# 2012_BALISE_CARTE_EMETTEUR.net
KiCad netlist of a schematic drawn in Altium Designer
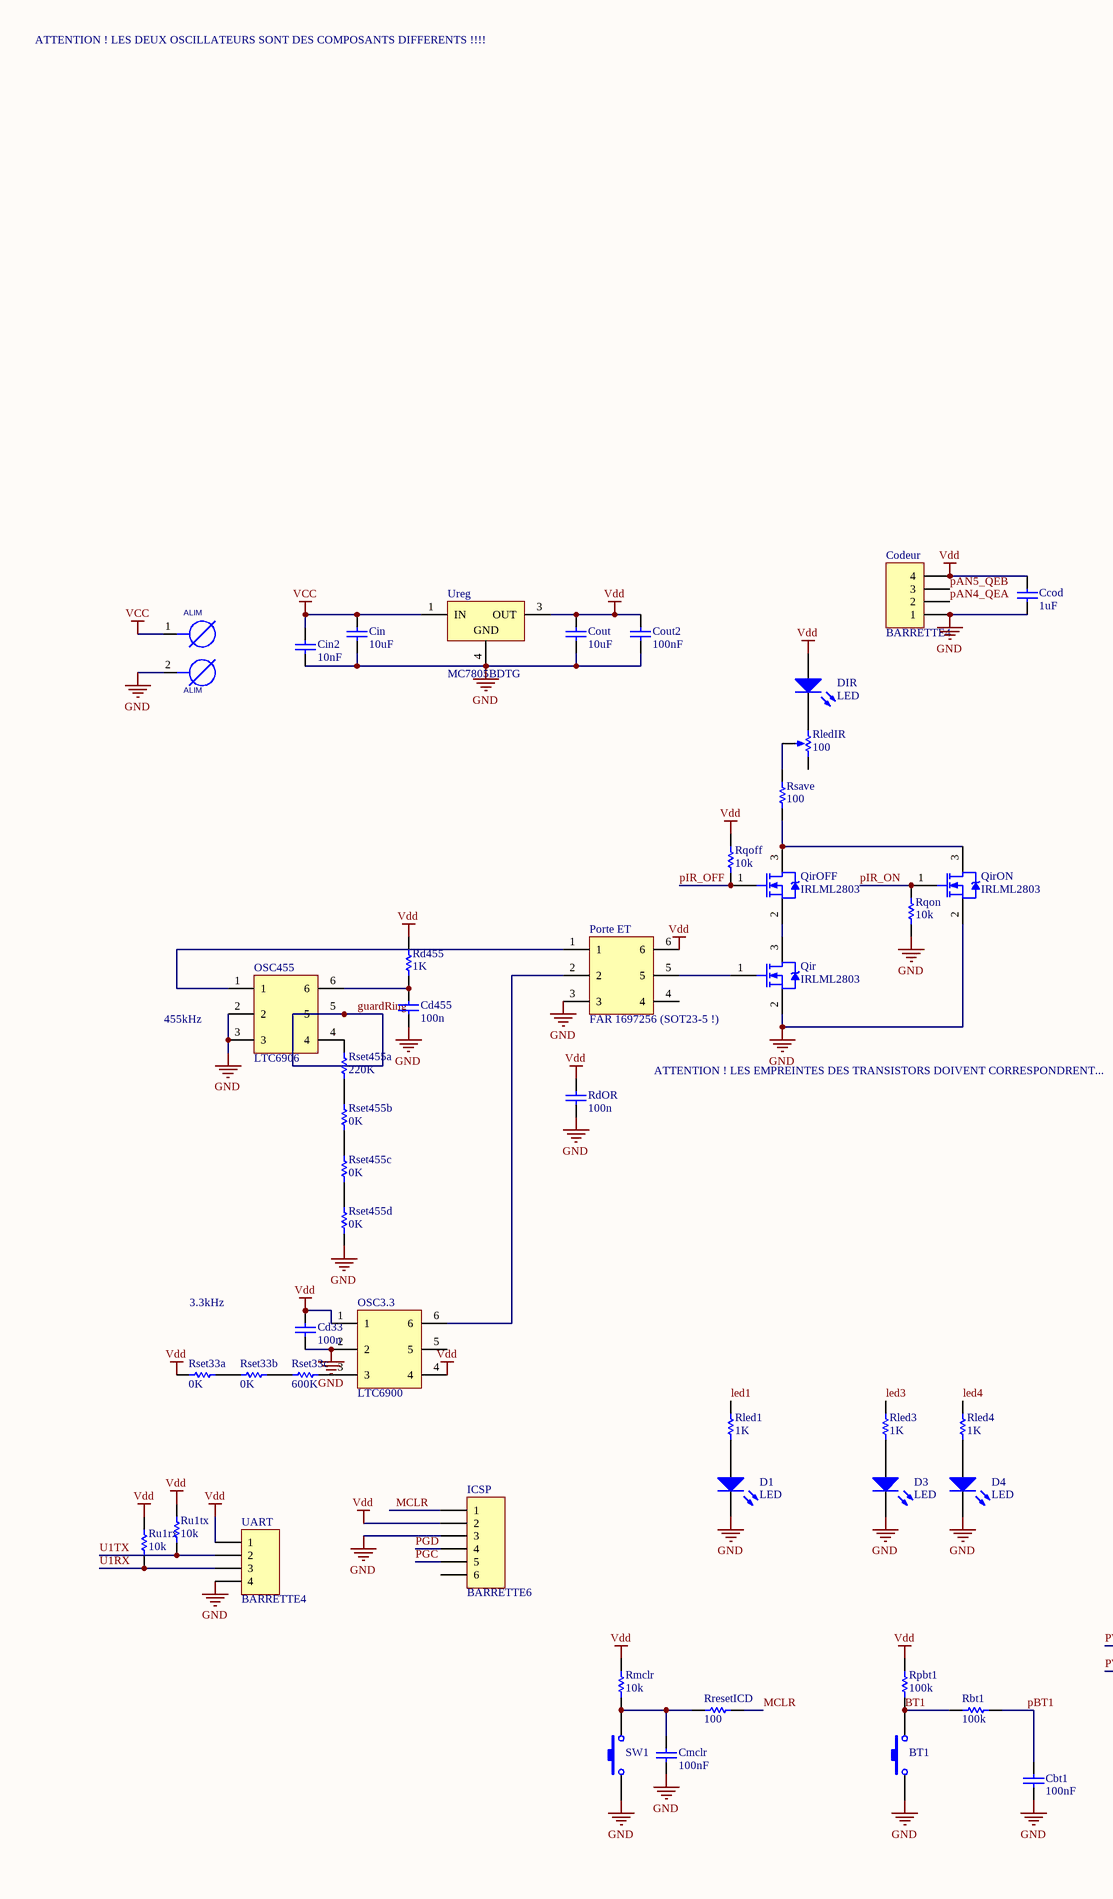
[diagram p0: 2012_BALISE_CARTE_EMETTEUR.SchDoc, left]
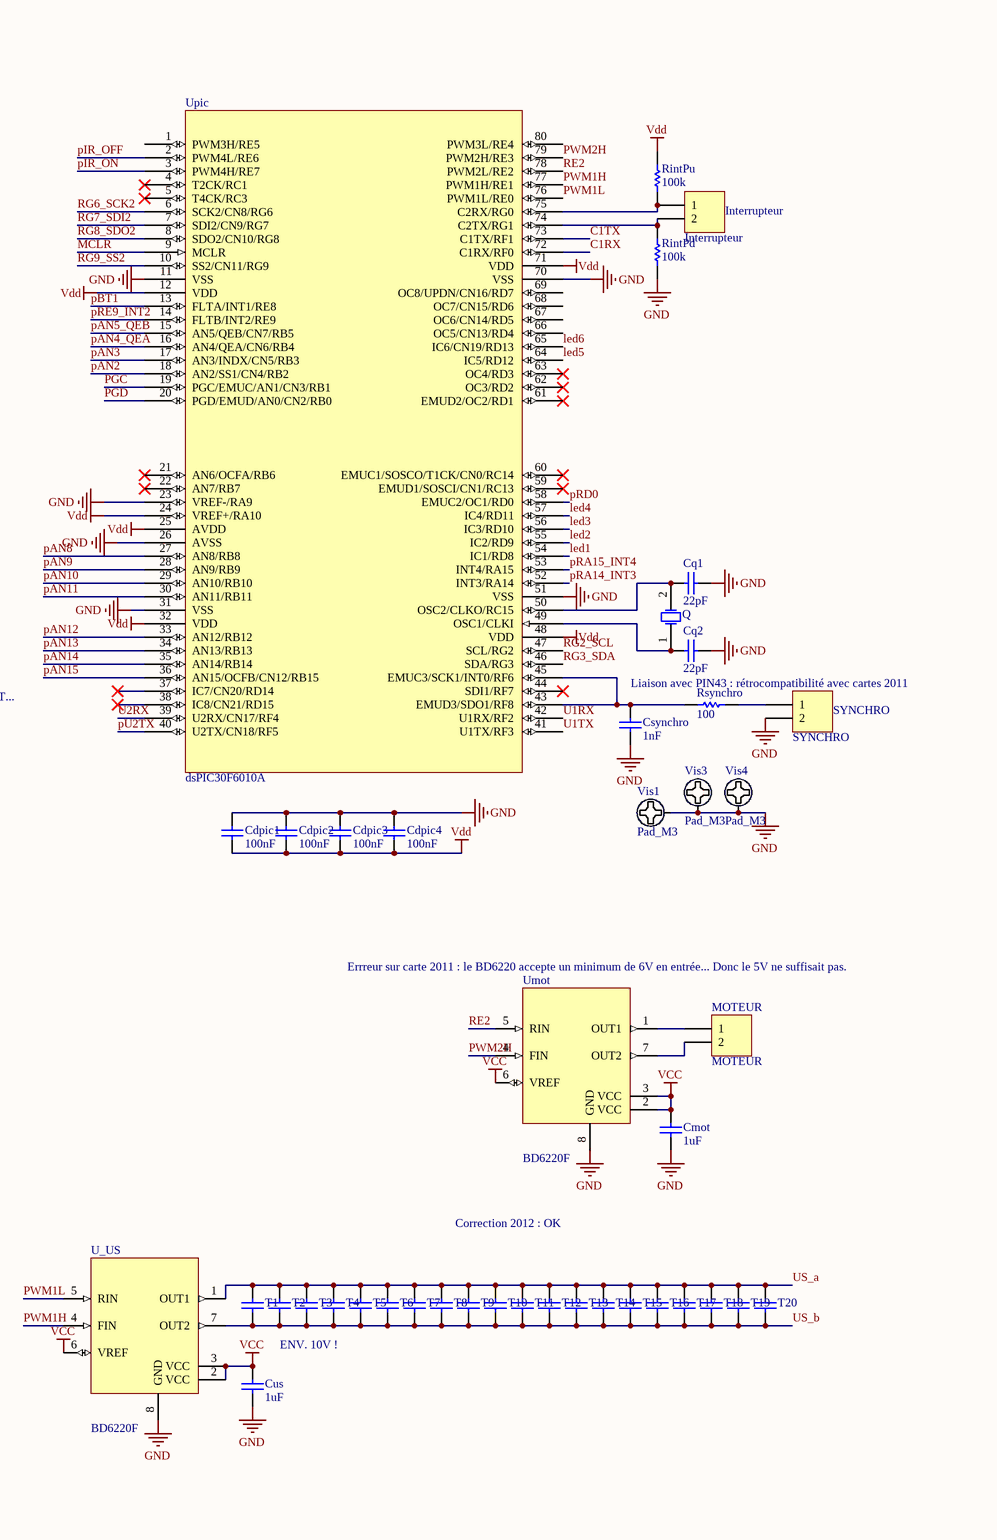
[diagram p1: 2012_BALISE_CARTE_EMETTEUR.SchDoc, middle]
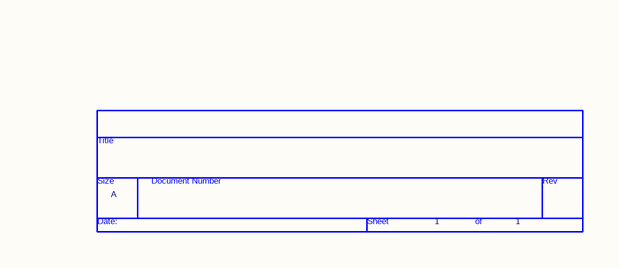
[diagram p2: 2012_BALISE_CARTE_EMETTEUR.SchDoc, right]

(export (version "E")
  (design (tool "Eeschema 10.0.6"))
  (components
    (comp (ref "*")
      (value "TitleBlock0")
      (fields (field (name "PAGE COUNT") "1") (field (name "PAGE NUMBER") "1") (field (name "PAGE SIZE") "A"))
      (libsource (lib "*") (part "TitleBlock0"))
    )
    (comp (ref "ALIM") (value "ALIM") (footprint "BORNIER2") (libsource (lib "*") (part "BORNIER2")))
    (comp (ref "BT1")
      (value "SW_Pushbutton_6x6mm_Vertical")
      (footprint "Switch 6x6 Vertical")
      (description "Switch tactil 6mm x 6mm Vertical")
      (fields (field (name "PUBLISHER") "Damien Guitton"))
      (libsource (lib "DG_Interrupteur") (part "SW_Pushbutton_6x6mm_Vertical"))
    )
    (comp (ref "Cbt1")
      (value "100nF")
      (footprint "C0805_N")
      (description "Capacitor")
      (fields (field (name "PUBLISHER") "Altium Limited"))
      (libsource (lib "DG_Condensateur") (part "Capacitor"))
    )
    (comp (ref "Ccod")
      (value "1uF")
      (footprint "C1206_N")
      (description "Capacitor")
      (fields (field (name "PUBLISHER") "Altium Limited"))
      (libsource (lib "_ROBOT") (part "Condensateur"))
    )
    (comp (ref "Cd33")
      (value "100n")
      (footprint "C0805_N")
      (description "Capacitor")
      (fields (field (name "PUBLISHER") "Altium Limited"))
      (libsource (lib "_ROBOT") (part "Condensateur"))
    )
    (comp (ref "Cd455")
      (value "100n")
      (footprint "C0805_N")
      (description "Capacitor")
      (fields (field (name "PUBLISHER") "Altium Limited"))
      (libsource (lib "_ROBOT") (part "Condensateur"))
    )
    (comp (ref "Cdpic1")
      (value "100nF")
      (footprint "C0805_N")
      (description "Capacitor")
      (fields (field (name "PUBLISHER") "Altium Limited"))
      (libsource (lib "DG_Condensateur") (part "Capacitor"))
    )
    (comp (ref "Cdpic2")
      (value "100nF")
      (footprint "C0805_N")
      (description "Capacitor")
      (fields (field (name "PUBLISHER") "Altium Limited"))
      (libsource (lib "DG_Condensateur") (part "Capacitor"))
    )
    (comp (ref "Cdpic3")
      (value "100nF")
      (footprint "C0805_N")
      (description "Capacitor")
      (fields (field (name "PUBLISHER") "Altium Limited"))
      (libsource (lib "DG_Condensateur") (part "Capacitor"))
    )
    (comp (ref "Cdpic4")
      (value "100nF")
      (footprint "C0805_N")
      (description "Capacitor")
      (fields (field (name "PUBLISHER") "Altium Limited"))
      (libsource (lib "DG_Condensateur") (part "Capacitor"))
    )
    (comp (ref "Cin")
      (value "10uF")
      (footprint "C1206_N")
      (description "Capacitor")
      (fields (field (name "PUBLISHER") "Altium Limited"))
      (libsource (lib "DG_Condensateur") (part "Capacitor"))
    )
    (comp (ref "Cin2")
      (value "10nF")
      (footprint "C0805_N")
      (description "Capacitor")
      (fields (field (name "PUBLISHER") "Altium Limited"))
      (libsource (lib "DG_Condensateur") (part "Capacitor"))
    )
    (comp (ref "Cmclr")
      (value "100nF")
      (footprint "C0805_N")
      (description "Capacitor")
      (fields (field (name "PUBLISHER") "Altium Limited"))
      (libsource (lib "DG_Condensateur") (part "Capacitor"))
    )
    (comp (ref "Cmot")
      (value "1uF")
      (footprint "C1206_N")
      (description "Capacitor")
      (fields (field (name "PUBLISHER") "Altium Limited"))
      (libsource (lib "_ROBOT") (part "Condensateur"))
    )
    (comp (ref "Codeur")
      (value "BARRETTE4")
      (footprint "HE14_4")
      (description "Header, 4-Pin")
      (fields (field (name "PUBLISHER") "Altium Limited"))
      (libsource (lib "") (part "BARRETTE4_1"))
    )
    (comp (ref "Cout")
      (value "10uF")
      (footprint "C1206_N")
      (description "Capacitor")
      (fields (field (name "PUBLISHER") "Altium Limited"))
      (libsource (lib "DG_Condensateur") (part "Capacitor"))
    )
    (comp (ref "Cout2")
      (value "100nF")
      (footprint "C0805_N")
      (description "Capacitor")
      (fields (field (name "PUBLISHER") "Altium Limited"))
      (libsource (lib "DG_Condensateur") (part "Capacitor"))
    )
    (comp (ref "Cq1")
      (value "22pF")
      (footprint "C0805_N")
      (description "Capacitor")
      (fields (field (name "PUBLISHER") "Altium Limited"))
      (libsource (lib "DG_Condensateur") (part "Capacitor"))
    )
    (comp (ref "Cq2")
      (value "22pF")
      (footprint "C0805_N")
      (description "Capacitor")
      (fields (field (name "PUBLISHER") "Altium Limited"))
      (libsource (lib "DG_Condensateur") (part "Capacitor"))
    )
    (comp (ref "Csynchro")
      (value "1nF")
      (footprint "C0805_N")
      (description "Capacitor")
      (fields (field (name "PUBLISHER") "Altium Limited"))
      (libsource (lib "DG_Condensateur") (part "Capacitor"))
    )
    (comp (ref "Cus")
      (value "1uF")
      (footprint "C1206_N")
      (description "Capacitor")
      (fields (field (name "PUBLISHER") "Altium Limited"))
      (libsource (lib "_ROBOT") (part "Condensateur"))
    )
    (comp (ref "D1")
      (value "LED")
      (footprint "LED_0805")
      (description "Typical LED")
      (fields (field (name "PUBLISHER") "Altium Limited"))
      (libsource (lib "DG_LED") (part "LED"))
    )
    (comp (ref "D3")
      (value "LED")
      (footprint "LED_0805")
      (description "Typical LED")
      (fields (field (name "PUBLISHER") "Altium Limited"))
      (libsource (lib "DG_LED") (part "LED"))
    )
    (comp (ref "D4")
      (value "LED")
      (footprint "LED_0805")
      (description "Typical LED")
      (fields (field (name "PUBLISHER") "Altium Limited"))
      (libsource (lib "DG_LED") (part "LED"))
    )
    (comp (ref "DIR")
      (value "LED")
      (footprint "LED5")
      (description "Typical RED, GREEN, YELLOW, AMBER GaAs LED")
      (fields (field (name "PUBLISHER") "Altium Limited"))
      (libsource (lib "Robot2010") (part "LED"))
    )
    (comp (ref "ICSP")
      (value "BARRETTE6")
      (footprint "HE14_6")
      (description "Header, 6-Pin")
      (fields (field (name "PUBLISHER") "Altium Limited"))
      (libsource (lib "Connecteur") (part "BARRETTE6"))
    )
    (comp (ref "Interrupteur")
      (value "Interrupteur")
      (footprint "Robot2010:HEADER2")
      (description "Header, 2-Pin")
      (fields (field (name "PUBLISHER") "Altium Limited"))
      (libsource (lib "Robot2010") (part "BARRETTE2"))
    )
    (comp (ref "MOTEUR")
      (value "MOTEUR")
      (footprint "Robot2010:HEADER2")
      (description "Header, 2-Pin")
      (fields (field (name "PUBLISHER") "Altium Limited"))
      (libsource (lib "Robot2010") (part "BARRETTE2"))
    )
    (comp (ref "OSC3.3")
      (value "LTC6900")
      (footprint "SOT23-6")
      (description "Header, 3-Pin, Dual row")
      (fields (field (name "PUBLISHER") "Altium Limited"))
      (libsource (lib "Robot2010") (part "SOT23-6"))
    )
    (comp (ref "OSC455")
      (value "LTC6906")
      (footprint "SOT23-6")
      (description "Header, 3-Pin, Dual row")
      (fields (field (name "PUBLISHER") "Altium Limited"))
      (libsource (lib "Robot2010") (part "SOT23-6"))
    )
    (comp (ref "Porte ET")
      (value "FAR 1697256 (SOT23-5 !)")
      (footprint "SOT23-6")
      (description "Header, 3-Pin, Dual row")
      (fields (field (name "PUBLISHER") "Altium Limited"))
      (libsource (lib "Robot2010") (part "SOT23-6"))
    )
    (comp (ref "Q")
      (value "QU")
      (footprint "HC49US")
      (description "Crystal Oscillator")
      (fields (field (name "PUBLISHER") "Altium Limited"))
      (libsource (lib "miniprojet") (part "QUARTZ_DROIT_BAS_PROFIL"))
    )
    (comp (ref "Qir")
      (value "IRLML2803")
      (footprint "SOT-23")
      (description "HEXFET Power MOSFET")
      (fields (field (name "PUBLISHER") "Altium Limited"))
      (libsource (lib "IR Discrete MOSFET - Power") (part "IRLML2803"))
    )
    (comp (ref "QirOFF")
      (value "IRLML2803")
      (footprint "SOT-23")
      (description "HEXFET Power MOSFET")
      (fields (field (name "PUBLISHER") "Altium Limited"))
      (libsource (lib "IR Discrete MOSFET - Power") (part "IRLML2803"))
    )
    (comp (ref "QirON")
      (value "IRLML2803")
      (footprint "SOT-23")
      (description "HEXFET Power MOSFET")
      (fields (field (name "PUBLISHER") "Altium Limited"))
      (libsource (lib "IR Discrete MOSFET - Power") (part "IRLML2803"))
    )
    (comp (ref "Rbt1")
      (value "100k")
      (footprint "R1206_N")
      (description "Resistor")
      (fields (field (name "PUBLISHER") "Altium Limited"))
      (libsource (lib "DG_Resistance") (part "Resistor"))
    )
    (comp (ref "Rd455")
      (value "1K")
      (footprint "R1206_N")
      (description "Resistor")
      (fields (field (name "PUBLISHER") "Altium Limited"))
      (libsource (lib "_ROBOT") (part "Resistor"))
    )
    (comp (ref "RdOR")
      (value "100n")
      (footprint "C0805_N")
      (description "Capacitor")
      (fields (field (name "PUBLISHER") "Altium Limited"))
      (libsource (lib "_ROBOT") (part "Condensateur"))
    )
    (comp (ref "RintPd")
      (value "100k")
      (footprint "R1206_N")
      (description "Resistor")
      (fields (field (name "PUBLISHER") "Altium Limited"))
      (libsource (lib "_ROBOT") (part "Resistor"))
    )
    (comp (ref "RintPu")
      (value "100k")
      (footprint "R1206_N")
      (description "Resistor")
      (fields (field (name "PUBLISHER") "Altium Limited"))
      (libsource (lib "_ROBOT") (part "Resistor"))
    )
    (comp (ref "Rled1")
      (value "1K")
      (footprint "R1206_N")
      (description "Resistor")
      (fields (field (name "PUBLISHER") "Altium Limited"))
      (libsource (lib "DG_Resistance") (part "Resistor"))
    )
    (comp (ref "Rled3")
      (value "1K")
      (footprint "R1206_N")
      (description "Resistor")
      (fields (field (name "PUBLISHER") "Altium Limited"))
      (libsource (lib "DG_Resistance") (part "Resistor"))
    )
    (comp (ref "Rled4")
      (value "1K")
      (footprint "R1206_N")
      (description "Resistor")
      (fields (field (name "PUBLISHER") "Altium Limited"))
      (libsource (lib "DG_Resistance") (part "Resistor"))
    )
    (comp (ref "RledIR")
      (value "100")
      (footprint "Trimmer_Bourns_3314G")
      (description "Trimmer monotour, Bourns,serie 3314P")
      (libsource (lib "DG_Resistance") (part "Trimmer monotour, Bourns,serie 3314P"))
    )
    (comp (ref "Rmclr")
      (value "10k")
      (footprint "R1206_N")
      (description "Resistor")
      (fields (field (name "PUBLISHER") "Altium Limited"))
      (libsource (lib "DG_Resistance") (part "Resistor"))
    )
    (comp (ref "Rpbt1")
      (value "100k")
      (footprint "R1206_N")
      (description "Resistor")
      (fields (field (name "PUBLISHER") "Altium Limited"))
      (libsource (lib "DG_Resistance") (part "Resistor"))
    )
    (comp (ref "Rqoff")
      (value "10k")
      (footprint "R1206_N")
      (description "Resistor")
      (fields (field (name "PUBLISHER") "Altium Limited"))
      (libsource (lib "_ROBOT") (part "Resistor"))
    )
    (comp (ref "Rqon")
      (value "10k")
      (footprint "R1206_N")
      (description "Resistor")
      (fields (field (name "PUBLISHER") "Altium Limited"))
      (libsource (lib "_ROBOT") (part "Resistor"))
    )
    (comp (ref "RresetICD")
      (value "100")
      (footprint "R1206_N")
      (description "Resistor")
      (fields (field (name "PUBLISHER") "Altium Limited"))
      (libsource (lib "DG_Resistance") (part "Resistor"))
    )
    (comp (ref "Rsave")
      (value "100")
      (footprint "R1206_N")
      (description "Resistor")
      (fields (field (name "PUBLISHER") "Altium Limited"))
      (libsource (lib "_ROBOT") (part "Resistor"))
    )
    (comp (ref "Rset33a")
      (value "0K")
      (footprint "R1206_N")
      (description "Resistor")
      (fields (field (name "PUBLISHER") "Altium Limited"))
      (libsource (lib "_ROBOT") (part "Resistor"))
    )
    (comp (ref "Rset33b")
      (value "0K")
      (footprint "R1206_N")
      (description "Resistor")
      (fields (field (name "PUBLISHER") "Altium Limited"))
      (libsource (lib "_ROBOT") (part "Resistor"))
    )
    (comp (ref "Rset33c")
      (value "600K")
      (footprint "R1206_N")
      (description "Resistor")
      (fields (field (name "PUBLISHER") "Altium Limited"))
      (libsource (lib "_ROBOT") (part "Resistor"))
    )
    (comp (ref "Rset455a")
      (value "220K")
      (footprint "R1206_N")
      (description "Resistor")
      (fields (field (name "PUBLISHER") "Altium Limited"))
      (libsource (lib "_ROBOT") (part "Resistor"))
    )
    (comp (ref "Rset455b")
      (value "0K")
      (footprint "R1206_N")
      (description "Resistor")
      (fields (field (name "PUBLISHER") "Altium Limited"))
      (libsource (lib "_ROBOT") (part "Resistor"))
    )
    (comp (ref "Rset455c")
      (value "0K")
      (footprint "R1206_N")
      (description "Resistor")
      (fields (field (name "PUBLISHER") "Altium Limited"))
      (libsource (lib "_ROBOT") (part "Resistor"))
    )
    (comp (ref "Rset455d")
      (value "0K")
      (footprint "R1206_N")
      (description "Resistor")
      (fields (field (name "PUBLISHER") "Altium Limited"))
      (libsource (lib "_ROBOT") (part "Resistor"))
    )
    (comp (ref "Rsynchro")
      (value "100")
      (footprint "R1206_N")
      (description "Resistor")
      (fields (field (name "PUBLISHER") "Altium Limited"))
      (libsource (lib "_ROBOT") (part "Resistor"))
    )
    (comp (ref "Ru1rx")
      (value "10k")
      (footprint "R1206_N")
      (description "Resistor")
      (fields (field (name "PUBLISHER") "Altium Limited"))
      (libsource (lib "DG_Resistance") (part "Resistor"))
    )
    (comp (ref "Ru1tx")
      (value "10k")
      (footprint "R1206_N")
      (description "Resistor")
      (fields (field (name "PUBLISHER") "Altium Limited"))
      (libsource (lib "DG_Resistance") (part "Resistor"))
    )
    (comp (ref "SW1")
      (value "SW_Pushbutton_6x6mm_Vertical")
      (footprint "Switch 6x6 Vertical")
      (description "Switch tactil 6mm x 6mm Vertical")
      (fields (field (name "PUBLISHER") "Damien Guitton"))
      (libsource (lib "DG_Interrupteur") (part "SW_Pushbutton_6x6mm_Vertical"))
    )
    (comp (ref "SYNCHRO")
      (value "SYNCHRO")
      (footprint "Robot2010:HEADER2")
      (description "Header, 2-Pin")
      (fields (field (name "PUBLISHER") "Altium Limited"))
      (libsource (lib "Robot2010") (part "BARRETTE2"))
    )
    (comp (ref "T1")
      (value "40kHz")
      (footprint "MA40S4R/S Transducteur US - 3D haut de carte")
      (description "Capacitor")
      (fields (field (name "PUBLISHER") "Altium Limited"))
      (libsource (lib "_ROBOT") (part "Condensateur"))
    )
    (comp (ref "T2")
      (value "40kHz")
      (footprint "MA40S4R/S Transducteur US - 3D haut de carte")
      (description "Capacitor")
      (fields (field (name "PUBLISHER") "Altium Limited"))
      (libsource (lib "_ROBOT") (part "Condensateur"))
    )
    (comp (ref "T3")
      (value "40kHz")
      (footprint "MA40S4R/S Transducteur US - 3D haut de carte")
      (description "Capacitor")
      (fields (field (name "PUBLISHER") "Altium Limited"))
      (libsource (lib "_ROBOT") (part "Condensateur"))
    )
    (comp (ref "T4")
      (value "40kHz")
      (footprint "MA40S4R/S Transducteur US - 3D haut de carte")
      (description "Capacitor")
      (fields (field (name "PUBLISHER") "Altium Limited"))
      (libsource (lib "_ROBOT") (part "Condensateur"))
    )
    (comp (ref "T5")
      (value "40kHz")
      (footprint "MA40S4R/S Transducteur US - 3D haut de carte")
      (description "Capacitor")
      (fields (field (name "PUBLISHER") "Altium Limited"))
      (libsource (lib "_ROBOT") (part "Condensateur"))
    )
    (comp (ref "T6")
      (value "40kHz")
      (footprint "MA40S4R/S Transducteur US - 3D haut de carte")
      (description "Capacitor")
      (fields (field (name "PUBLISHER") "Altium Limited"))
      (libsource (lib "_ROBOT") (part "Condensateur"))
    )
    (comp (ref "T7")
      (value "40kHz")
      (footprint "MA40S4R/S Transducteur US - 3D haut de carte")
      (description "Capacitor")
      (fields (field (name "PUBLISHER") "Altium Limited"))
      (libsource (lib "_ROBOT") (part "Condensateur"))
    )
    (comp (ref "T8")
      (value "40kHz")
      (footprint "MA40S4R/S Transducteur US - 3D haut de carte")
      (description "Capacitor")
      (fields (field (name "PUBLISHER") "Altium Limited"))
      (libsource (lib "_ROBOT") (part "Condensateur"))
    )
    (comp (ref "T9")
      (value "40kHz")
      (footprint "MA40S4R/S Transducteur US - 3D haut de carte")
      (description "Capacitor")
      (fields (field (name "PUBLISHER") "Altium Limited"))
      (libsource (lib "_ROBOT") (part "Condensateur"))
    )
    (comp (ref "T10")
      (value "40kHz")
      (footprint "MA40S4R/S Transducteur US - 3D haut de carte")
      (description "Capacitor")
      (fields (field (name "PUBLISHER") "Altium Limited"))
      (libsource (lib "_ROBOT") (part "Condensateur"))
    )
    (comp (ref "T11")
      (value "40kHz")
      (footprint "MA40S4R/S Transducteur US - 3D haut de carte")
      (description "Capacitor")
      (fields (field (name "PUBLISHER") "Altium Limited"))
      (libsource (lib "_ROBOT") (part "Condensateur"))
    )
    (comp (ref "T12")
      (value "40kHz")
      (footprint "MA40S4R/S Transducteur US - 3D haut de carte")
      (description "Capacitor")
      (fields (field (name "PUBLISHER") "Altium Limited"))
      (libsource (lib "_ROBOT") (part "Condensateur"))
    )
    (comp (ref "T13")
      (value "40kHz")
      (footprint "MA40S4R/S Transducteur US - 3D haut de carte")
      (description "Capacitor")
      (fields (field (name "PUBLISHER") "Altium Limited"))
      (libsource (lib "_ROBOT") (part "Condensateur"))
    )
    (comp (ref "T14")
      (value "40kHz")
      (footprint "MA40S4R/S Transducteur US - 3D haut de carte")
      (description "Capacitor")
      (fields (field (name "PUBLISHER") "Altium Limited"))
      (libsource (lib "_ROBOT") (part "Condensateur"))
    )
    (comp (ref "T15")
      (value "40kHz")
      (footprint "MA40S4R/S Transducteur US - 3D haut de carte")
      (description "Capacitor")
      (fields (field (name "PUBLISHER") "Altium Limited"))
      (libsource (lib "_ROBOT") (part "Condensateur"))
    )
    (comp (ref "T16")
      (value "40kHz")
      (footprint "MA40S4R/S Transducteur US - 3D haut de carte")
      (description "Capacitor")
      (fields (field (name "PUBLISHER") "Altium Limited"))
      (libsource (lib "_ROBOT") (part "Condensateur"))
    )
    (comp (ref "T17")
      (value "40kHz")
      (footprint "MA40S4R/S Transducteur US - 3D haut de carte")
      (description "Capacitor")
      (fields (field (name "PUBLISHER") "Altium Limited"))
      (libsource (lib "_ROBOT") (part "Condensateur"))
    )
    (comp (ref "T18")
      (value "40kHz")
      (footprint "MA40S4R/S Transducteur US - 3D haut de carte")
      (description "Capacitor")
      (fields (field (name "PUBLISHER") "Altium Limited"))
      (libsource (lib "_ROBOT") (part "Condensateur"))
    )
    (comp (ref "T19")
      (value "40kHz")
      (footprint "MA40S4R/S Transducteur US - 3D haut de carte")
      (description "Capacitor")
      (fields (field (name "PUBLISHER") "Altium Limited"))
      (libsource (lib "_ROBOT") (part "Condensateur"))
    )
    (comp (ref "T20")
      (value "40kHz")
      (footprint "MA40S4R/S Transducteur US - 3D haut de carte")
      (description "Capacitor")
      (fields (field (name "PUBLISHER") "Altium Limited"))
      (libsource (lib "_ROBOT") (part "Condensateur"))
    )
    (comp (ref "UART")
      (value "BARRETTE4")
      (footprint "HE14_4")
      (description "Header, 4-Pin")
      (fields (field (name "PUBLISHER") "Altium Limited"))
      (libsource (lib "Connecteur") (part "BARRETTE4"))
    )
    (comp (ref "Umot")
      (value "BD6220F")
      (footprint "SO8_N")
      (description "H Bridge - 2A")
      (libsource (lib "Circuit intégré") (part "BD6220F"))
    )
    (comp (ref "Upic")
      (value "dsPIC30F6010A")
      (footprint "TQFP80_N")
      (description "High-Performance, 16-bit Digital Signal Controllers")
      (libsource (lib "DG_Microcontroleur") (part "dsPIC30F6010A"))
    )
    (comp (ref "Ureg")
      (value "MC7805BDTG")
      (footprint "369A-13")
      (description "Three-Terminal Positive Voltage Regulator")
      (fields (field (name "PUBLISHER") "Altium Limited"))
      (libsource (lib "ON Semi Power Mgt Voltage Regulator") (part "MC7805ACD2T"))
    )
    (comp (ref "U_US")
      (value "BD6220F")
      (footprint "SO8_N")
      (description "H Bridge - 2A")
      (libsource (lib "Circuit intégré") (part "BD6220F"))
    )
    (comp (ref "Vis1")
      (value "Pad_M3")
      (footprint "M3x6mm")
      (description "Vis M3 X 6mm _TORX_Tête 6mm")
      (fields (field (name "PUBLISHER") "Damien Guitton"))
      (libsource (lib "DG_Mecanique") (part "Vis M3 X 6mm _TORX_Tête 6mm"))
    )
    (comp (ref "Vis3")
      (value "Pad_M3")
      (footprint "M3x6mm")
      (description "Vis M3 X 6mm _TORX_Tête 6mm")
      (fields (field (name "PUBLISHER") "Damien Guitton"))
      (libsource (lib "DG_Mecanique") (part "Vis M3 X 6mm _TORX_Tête 6mm"))
    )
    (comp (ref "Vis4")
      (value "Pad_M3")
      (footprint "M3x6mm")
      (description "Vis M3 X 6mm _TORX_Tête 6mm")
      (fields (field (name "PUBLISHER") "Damien Guitton"))
      (libsource (lib "DG_Mecanique") (part "Vis M3 X 6mm _TORX_Tête 6mm"))
    )
  )
  (nets
    (net (code "1") (name "/BT1") (class "Default")
      (node (ref "BT1") (pin "3") (pinfunction "3_3") (pintype "passive"))
      (node (ref "Rbt1") (pin "2") (pinfunction "2_2") (pintype "passive"))
      (node (ref "Rpbt1") (pin "1") (pinfunction "1_1") (pintype "passive"))
    )
    (net (code "2") (name "/C1RX") (class "Default")
      (node (ref "Upic") (pin "72") (pinfunction "C1RX/RF0_72") (pintype "bidirectional"))
    )
    (net (code "3") (name "/C1TX") (class "Default")
      (node (ref "Upic") (pin "73") (pinfunction "C1TX/RF1_73") (pintype "bidirectional"))
    )
    (net (code "4") (name "/MCLR") (class "Default")
      (node (ref "ICSP") (pin "1") (pinfunction "1_1") (pintype "passive"))
      (node (ref "RresetICD") (pin "1") (pinfunction "1_1") (pintype "passive"))
      (node (ref "Upic") (pin "9") (pinfunction "MCLR_9") (pintype "input"))
    )
    (net (code "5") (name "/PGC") (class "Default")
      (node (ref "ICSP") (pin "5") (pinfunction "5_5") (pintype "passive"))
      (node (ref "Upic") (pin "19") (pinfunction "PGC/EMUC/AN1/CN3/RB1_19") (pintype "bidirectional"))
    )
    (net (code "6") (name "/PGD") (class "Default")
      (node (ref "ICSP") (pin "4") (pinfunction "4_4") (pintype "passive"))
      (node (ref "Upic") (pin "20") (pinfunction "PGD/EMUD/AN0/CN2/RB0_20") (pintype "bidirectional"))
    )
    (net (code "7") (name "/PWM1H") (class "Default")
      (node (ref "U_US") (pin "4") (pinfunction "FIN_4") (pintype "input"))
      (node (ref "Upic") (pin "77") (pinfunction "PWM1H/RE1_77") (pintype "bidirectional"))
    )
    (net (code "8") (name "/PWM1L") (class "Default")
      (node (ref "U_US") (pin "5") (pinfunction "RIN_5") (pintype "input"))
      (node (ref "Upic") (pin "76") (pinfunction "PWM1L/RE0_76") (pintype "bidirectional"))
    )
    (net (code "9") (name "/PWM2H") (class "Default")
      (node (ref "Umot") (pin "4") (pinfunction "FIN_4") (pintype "input"))
      (node (ref "Upic") (pin "79") (pinfunction "PWM2H/RE3_79") (pintype "bidirectional"))
    )
    (net (code "10") (name "/RE2") (class "Default")
      (node (ref "Umot") (pin "5") (pinfunction "RIN_5") (pintype "input"))
      (node (ref "Upic") (pin "78") (pinfunction "PWM2L/RE2_78") (pintype "bidirectional"))
    )
    (net (code "11") (name "/RG2_SCL") (class "Default")
      (node (ref "Upic") (pin "47") (pinfunction "SCL/RG2_47") (pintype "bidirectional"))
    )
    (net (code "12") (name "/RG3_SDA") (class "Default")
      (node (ref "Upic") (pin "46") (pinfunction "SDA/RG3_46") (pintype "bidirectional"))
    )
    (net (code "13") (name "/RG6_SCK2") (class "Default")
      (node (ref "Upic") (pin "6") (pinfunction "SCK2/CN8/RG6_6") (pintype "bidirectional"))
    )
    (net (code "14") (name "/RG7_SDI2") (class "Default")
      (node (ref "Upic") (pin "7") (pinfunction "SDI2/CN9/RG7_7") (pintype "bidirectional"))
    )
    (net (code "15") (name "/RG8_SDO2") (class "Default")
      (node (ref "Upic") (pin "8") (pinfunction "SDO2/CN10/RG8_8") (pintype "bidirectional"))
    )
    (net (code "16") (name "/RG9_SS2") (class "Default")
      (node (ref "Upic") (pin "10") (pinfunction "SS2/CN11/RG9_10") (pintype "bidirectional"))
    )
    (net (code "17") (name "/U1RX") (class "Default")
      (node (ref "Ru1rx") (pin "1") (pinfunction "1_1") (pintype "passive"))
      (node (ref "UART") (pin "3") (pinfunction "3_3") (pintype "passive"))
      (node (ref "Upic") (pin "42") (pinfunction "U1RX/RF2_42") (pintype "bidirectional"))
    )
    (net (code "18") (name "/U1TX") (class "Default")
      (node (ref "Ru1tx") (pin "1") (pinfunction "1_1") (pintype "passive"))
      (node (ref "UART") (pin "2") (pinfunction "2_2") (pintype "passive"))
      (node (ref "Upic") (pin "41") (pinfunction "U1TX/RF3_41") (pintype "bidirectional"))
    )
    (net (code "19") (name "/U2RX") (class "Default")
      (node (ref "Upic") (pin "39") (pinfunction "U2RX/CN17/RF4_39") (pintype "bidirectional"))
    )
    (net (code "20") (name "/US_a") (class "Default")
      (node (ref "T1") (pin "2") (pinfunction "2_2") (pintype "passive"))
      (node (ref "T10") (pin "2") (pinfunction "2_2") (pintype "passive"))
      (node (ref "T11") (pin "2") (pinfunction "2_2") (pintype "passive"))
      (node (ref "T12") (pin "2") (pinfunction "2_2") (pintype "passive"))
      (node (ref "T13") (pin "2") (pinfunction "2_2") (pintype "passive"))
      (node (ref "T14") (pin "2") (pinfunction "2_2") (pintype "passive"))
      (node (ref "T15") (pin "2") (pinfunction "2_2") (pintype "passive"))
      (node (ref "T16") (pin "2") (pinfunction "2_2") (pintype "passive"))
      (node (ref "T17") (pin "2") (pinfunction "2_2") (pintype "passive"))
      (node (ref "T18") (pin "2") (pinfunction "2_2") (pintype "passive"))
      (node (ref "T19") (pin "2") (pinfunction "2_2") (pintype "passive"))
      (node (ref "T2") (pin "2") (pinfunction "2_2") (pintype "passive"))
      (node (ref "T20") (pin "2") (pinfunction "2_2") (pintype "passive"))
      (node (ref "T3") (pin "2") (pinfunction "2_2") (pintype "passive"))
      (node (ref "T4") (pin "2") (pinfunction "2_2") (pintype "passive"))
      (node (ref "T5") (pin "2") (pinfunction "2_2") (pintype "passive"))
      (node (ref "T6") (pin "2") (pinfunction "2_2") (pintype "passive"))
      (node (ref "T7") (pin "2") (pinfunction "2_2") (pintype "passive"))
      (node (ref "T8") (pin "2") (pinfunction "2_2") (pintype "passive"))
      (node (ref "T9") (pin "2") (pinfunction "2_2") (pintype "passive"))
      (node (ref "U_US") (pin "1") (pinfunction "OUT1_1") (pintype "output"))
    )
    (net (code "21") (name "/US_b") (class "Default")
      (node (ref "T1") (pin "1") (pinfunction "1_1") (pintype "passive"))
      (node (ref "T10") (pin "1") (pinfunction "1_1") (pintype "passive"))
      (node (ref "T11") (pin "1") (pinfunction "1_1") (pintype "passive"))
      (node (ref "T12") (pin "1") (pinfunction "1_1") (pintype "passive"))
      (node (ref "T13") (pin "1") (pinfunction "1_1") (pintype "passive"))
      (node (ref "T14") (pin "1") (pinfunction "1_1") (pintype "passive"))
      (node (ref "T15") (pin "1") (pinfunction "1_1") (pintype "passive"))
      (node (ref "T16") (pin "1") (pinfunction "1_1") (pintype "passive"))
      (node (ref "T17") (pin "1") (pinfunction "1_1") (pintype "passive"))
      (node (ref "T18") (pin "1") (pinfunction "1_1") (pintype "passive"))
      (node (ref "T19") (pin "1") (pinfunction "1_1") (pintype "passive"))
      (node (ref "T2") (pin "1") (pinfunction "1_1") (pintype "passive"))
      (node (ref "T20") (pin "1") (pinfunction "1_1") (pintype "passive"))
      (node (ref "T3") (pin "1") (pinfunction "1_1") (pintype "passive"))
      (node (ref "T4") (pin "1") (pinfunction "1_1") (pintype "passive"))
      (node (ref "T5") (pin "1") (pinfunction "1_1") (pintype "passive"))
      (node (ref "T6") (pin "1") (pinfunction "1_1") (pintype "passive"))
      (node (ref "T7") (pin "1") (pinfunction "1_1") (pintype "passive"))
      (node (ref "T8") (pin "1") (pinfunction "1_1") (pintype "passive"))
      (node (ref "T9") (pin "1") (pinfunction "1_1") (pintype "passive"))
      (node (ref "U_US") (pin "7") (pinfunction "OUT2_7") (pintype "output"))
    )
    (net (code "22") (name "/guardRing") (class "Default")
      (node (ref "OSC455") (pin "5") (pinfunction "5_5") (pintype "passive"))
    )
    (net (code "23") (name "/led1") (class "Default")
      (node (ref "Rled1") (pin "2") (pinfunction "2_2") (pintype "passive"))
      (node (ref "Upic") (pin "54") (pinfunction "IC1/RD8_54") (pintype "bidirectional"))
    )
    (net (code "24") (name "/led2") (class "Default")
      (node (ref "Upic") (pin "55") (pinfunction "IC2/RD9_55") (pintype "bidirectional"))
    )
    (net (code "25") (name "/led3") (class "Default")
      (node (ref "Rled3") (pin "2") (pinfunction "2_2") (pintype "passive"))
      (node (ref "Upic") (pin "56") (pinfunction "IC3/RD10_56") (pintype "bidirectional"))
    )
    (net (code "26") (name "/led4") (class "Default")
      (node (ref "Rled4") (pin "2") (pinfunction "2_2") (pintype "passive"))
      (node (ref "Upic") (pin "57") (pinfunction "IC4/RD11_57") (pintype "bidirectional"))
    )
    (net (code "27") (name "/led5") (class "Default")
      (node (ref "Upic") (pin "64") (pinfunction "IC5/RD12_64") (pintype "bidirectional"))
    )
    (net (code "28") (name "/led6") (class "Default")
      (node (ref "Upic") (pin "65") (pinfunction "IC6/CN19/RD13_65") (pintype "bidirectional"))
    )
    (net (code "29") (name "/pAN2") (class "Default")
      (node (ref "Upic") (pin "18") (pinfunction "AN2/SS1/CN4/RB2_18") (pintype "bidirectional"))
    )
    (net (code "30") (name "/pAN3") (class "Default")
      (node (ref "Upic") (pin "17") (pinfunction "AN3/INDX/CN5/RB3_17") (pintype "bidirectional"))
    )
    (net (code "31") (name "/pAN4_QEA") (class "Default")
      (node (ref "Codeur") (pin "2") (pinfunction "2_2") (pintype "passive"))
      (node (ref "Upic") (pin "16") (pinfunction "AN4/QEA/CN6/RB4_16") (pintype "bidirectional"))
    )
    (net (code "32") (name "/pAN5_QEB") (class "Default")
      (node (ref "Codeur") (pin "3") (pinfunction "3_3") (pintype "passive"))
      (node (ref "Upic") (pin "15") (pinfunction "AN5/QEB/CN7/RB5_15") (pintype "bidirectional"))
    )
    (net (code "33") (name "/pAN8") (class "Default")
      (node (ref "Upic") (pin "27") (pinfunction "AN8/RB8_27") (pintype "bidirectional"))
    )
    (net (code "34") (name "/pAN9") (class "Default")
      (node (ref "Upic") (pin "28") (pinfunction "AN9/RB9_28") (pintype "bidirectional"))
    )
    (net (code "35") (name "/pAN10") (class "Default")
      (node (ref "Upic") (pin "29") (pinfunction "AN10/RB10_29") (pintype "bidirectional"))
    )
    (net (code "36") (name "/pAN11") (class "Default")
      (node (ref "Upic") (pin "30") (pinfunction "AN11/RB11_30") (pintype "bidirectional"))
    )
    (net (code "37") (name "/pAN12") (class "Default")
      (node (ref "Upic") (pin "33") (pinfunction "AN12/RB12_33") (pintype "bidirectional"))
    )
    (net (code "38") (name "/pAN13") (class "Default")
      (node (ref "Upic") (pin "34") (pinfunction "AN13/RB13_34") (pintype "bidirectional"))
    )
    (net (code "39") (name "/pAN14") (class "Default")
      (node (ref "Upic") (pin "35") (pinfunction "AN14/RB14_35") (pintype "bidirectional"))
    )
    (net (code "40") (name "/pAN15") (class "Default")
      (node (ref "Upic") (pin "36") (pinfunction "AN15/OCFB/CN12/RB15_36") (pintype "bidirectional"))
    )
    (net (code "41") (name "/pBT1") (class "Default")
      (node (ref "Cbt1") (pin "2") (pinfunction "2_2") (pintype "passive"))
      (node (ref "Rbt1") (pin "1") (pinfunction "1_1") (pintype "passive"))
      (node (ref "Upic") (pin "13") (pinfunction "FLTA/INT1/RE8_13") (pintype "bidirectional"))
    )
    (net (code "42") (name "/pIR_OFF") (class "Default")
      (node (ref "QirOFF") (pin "1") (pinfunction "G_1") (pintype "passive"))
      (node (ref "Rqoff") (pin "1") (pinfunction "1_1") (pintype "passive"))
      (node (ref "Upic") (pin "2") (pinfunction "PWM4L/RE6_2") (pintype "bidirectional"))
    )
    (net (code "43") (name "/pIR_ON") (class "Default")
      (node (ref "QirON") (pin "1") (pinfunction "G_1") (pintype "passive"))
      (node (ref "Rqon") (pin "2") (pinfunction "2_2") (pintype "passive"))
      (node (ref "Upic") (pin "3") (pinfunction "PWM4H/RE7_3") (pintype "bidirectional"))
    )
    (net (code "44") (name "/pRA14_INT3") (class "Default")
      (node (ref "Upic") (pin "52") (pinfunction "INT3/RA14_52") (pintype "bidirectional"))
    )
    (net (code "45") (name "/pRA15_INT4") (class "Default")
      (node (ref "Upic") (pin "53") (pinfunction "INT4/RA15_53") (pintype "bidirectional"))
    )
    (net (code "46") (name "/pRD0") (class "Default")
      (node (ref "Upic") (pin "58") (pinfunction "EMUC2/OC1/RD0_58") (pintype "bidirectional"))
    )
    (net (code "47") (name "/pRE9_INT2") (class "Default")
      (node (ref "Upic") (pin "14") (pinfunction "FLTB/INT2/RE9_14") (pintype "bidirectional"))
    )
    (net (code "48") (name "/pU2TX") (class "Default")
      (node (ref "Upic") (pin "40") (pinfunction "U2TX/CN18/RF5_40") (pintype "bidirectional"))
    )
    (net (code "49") (name "GND") (class "Default")
      (node (ref "ALIM") (pin "2") (pinfunction "B2_2") (pintype "passive"))
      (node (ref "BT1") (pin "1") (pinfunction "1_1") (pintype "passive"))
      (node (ref "Cbt1") (pin "1") (pinfunction "1_1") (pintype "passive"))
      (node (ref "Ccod") (pin "1") (pinfunction "1_1") (pintype "passive"))
      (node (ref "Cd33") (pin "1") (pinfunction "1_1") (pintype "passive"))
      (node (ref "Cd455") (pin "1") (pinfunction "1_1") (pintype "passive"))
      (node (ref "Cdpic1") (pin "2") (pinfunction "2_2") (pintype "passive"))
      (node (ref "Cdpic2") (pin "2") (pinfunction "2_2") (pintype "passive"))
      (node (ref "Cdpic3") (pin "2") (pinfunction "2_2") (pintype "passive"))
      (node (ref "Cdpic4") (pin "2") (pinfunction "2_2") (pintype "passive"))
      (node (ref "Cin") (pin "1") (pinfunction "1_1") (pintype "passive"))
      (node (ref "Cin2") (pin "1") (pinfunction "1_1") (pintype "passive"))
      (node (ref "Cmclr") (pin "1") (pinfunction "1_1") (pintype "passive"))
      (node (ref "Cmot") (pin "1") (pinfunction "1_1") (pintype "passive"))
      (node (ref "Codeur") (pin "1") (pinfunction "1_1") (pintype "passive"))
      (node (ref "Cout") (pin "1") (pinfunction "1_1") (pintype "passive"))
      (node (ref "Cout2") (pin "1") (pinfunction "1_1") (pintype "passive"))
      (node (ref "Cq1") (pin "2") (pinfunction "2_2") (pintype "passive"))
      (node (ref "Cq2") (pin "2") (pinfunction "2_2") (pintype "passive"))
      (node (ref "Csynchro") (pin "1") (pinfunction "1_1") (pintype "passive"))
      (node (ref "Cus") (pin "1") (pinfunction "1_1") (pintype "passive"))
      (node (ref "D1") (pin "2") (pinfunction "2_2") (pintype "passive"))
      (node (ref "D3") (pin "2") (pinfunction "2_2") (pintype "passive"))
      (node (ref "D4") (pin "2") (pinfunction "2_2") (pintype "passive"))
      (node (ref "ICSP") (pin "3") (pinfunction "3_3") (pintype "passive"))
      (node (ref "OSC3.3") (pin "2") (pinfunction "2_2") (pintype "passive"))
      (node (ref "OSC455") (pin "2") (pinfunction "2_2") (pintype "passive"))
      (node (ref "OSC455") (pin "3") (pinfunction "3_3") (pintype "passive"))
      (node (ref "Porte ET") (pin "3") (pinfunction "3_3") (pintype "passive"))
      (node (ref "Qir") (pin "2") (pinfunction "S_2") (pintype "passive"))
      (node (ref "QirON") (pin "2") (pinfunction "S_2") (pintype "passive"))
      (node (ref "RdOR") (pin "1") (pinfunction "1_1") (pintype "passive"))
      (node (ref "RintPd") (pin "2") (pinfunction "2_2") (pintype "passive"))
      (node (ref "Rqon") (pin "1") (pinfunction "1_1") (pintype "passive"))
      (node (ref "Rset455d") (pin "1") (pinfunction "1_1") (pintype "passive"))
      (node (ref "SW1") (pin "1") (pinfunction "1_1") (pintype "passive"))
      (node (ref "SYNCHRO") (pin "2") (pinfunction "2_2") (pintype "passive"))
      (node (ref "UART") (pin "4") (pinfunction "4_4") (pintype "passive"))
      (node (ref "U_US") (pin "8") (pinfunction "GND_8") (pintype "power_in"))
      (node (ref "Umot") (pin "8") (pinfunction "GND_8") (pintype "power_in"))
      (node (ref "Upic") (pin "11") (pinfunction "VSS_11") (pintype "power_in"))
      (node (ref "Upic") (pin "23") (pinfunction "VREF-/RA9_23") (pintype "bidirectional"))
      (node (ref "Upic") (pin "26") (pinfunction "AVSS_26") (pintype "power_in"))
      (node (ref "Upic") (pin "31") (pinfunction "VSS_31") (pintype "power_in"))
      (node (ref "Upic") (pin "51") (pinfunction "VSS_51") (pintype "power_in"))
      (node (ref "Upic") (pin "70") (pinfunction "VSS_70") (pintype "power_in"))
      (node (ref "Ureg") (pin "4") (pinfunction "GND_4") (pintype "power_in"))
      (node (ref "Vis1") (pin "1") (pinfunction "1_1") (pintype "passive"))
      (node (ref "Vis3") (pin "1") (pinfunction "1_1") (pintype "passive"))
      (node (ref "Vis4") (pin "1") (pinfunction "1_1") (pintype "passive"))
    )
    (net (code "50") (name "Net-(Cd455-Pad2)") (class "Default")
      (node (ref "Cd455") (pin "2") (pinfunction "2_2") (pintype "passive"))
      (node (ref "OSC455") (pin "6") (pinfunction "6_6") (pintype "passive"))
      (node (ref "Rd455") (pin "1") (pinfunction "1_1") (pintype "passive"))
    )
    (net (code "51") (name "Net-(Cmclr-Pad2)") (class "Default")
      (node (ref "Cmclr") (pin "2") (pinfunction "2_2") (pintype "passive"))
      (node (ref "Rmclr") (pin "1") (pinfunction "1_1") (pintype "passive"))
      (node (ref "RresetICD") (pin "2") (pinfunction "2_2") (pintype "passive"))
      (node (ref "SW1") (pin "3") (pinfunction "3_3") (pintype "passive"))
    )
    (net (code "52") (name "Net-(D1-Pad1)") (class "Default")
      (node (ref "D1") (pin "1") (pinfunction "1_1") (pintype "passive"))
      (node (ref "Rled1") (pin "1") (pinfunction "1_1") (pintype "passive"))
    )
    (net (code "53") (name "Net-(D3-Pad1)") (class "Default")
      (node (ref "D3") (pin "1") (pinfunction "1_1") (pintype "passive"))
      (node (ref "Rled3") (pin "1") (pinfunction "1_1") (pintype "passive"))
    )
    (net (code "54") (name "Net-(D4-Pad1)") (class "Default")
      (node (ref "D4") (pin "1") (pinfunction "1_1") (pintype "passive"))
      (node (ref "Rled4") (pin "1") (pinfunction "1_1") (pintype "passive"))
    )
    (net (code "55") (name "Net-(OSC3.3-Pad3)") (class "Default")
      (node (ref "OSC3.3") (pin "3") (pinfunction "3_3") (pintype "passive"))
      (node (ref "Rset33c") (pin "1") (pinfunction "1_1") (pintype "passive"))
    )
    (net (code "56") (name "Net-(OSC3.3-Pad6)") (class "Default")
      (node (ref "OSC3.3") (pin "6") (pinfunction "6_6") (pintype "passive"))
      (node (ref "Porte ET") (pin "2") (pinfunction "2_2") (pintype "passive"))
    )
    (net (code "57") (name "Net-(OSC455-Pad1)") (class "Default")
      (node (ref "OSC455") (pin "1") (pinfunction "1_1") (pintype "passive"))
      (node (ref "Porte ET") (pin "1") (pinfunction "1_1") (pintype "passive"))
    )
    (net (code "58") (name "Net-(OSC455-Pad4)") (class "Default")
      (node (ref "OSC455") (pin "4") (pinfunction "4_4") (pintype "passive"))
      (node (ref "Rset455a") (pin "2") (pinfunction "2_2") (pintype "passive"))
    )
    (net (code "59") (name "Net-(Q-OSC1)") (class "Default")
      (node (ref "Cq2") (pin "1") (pinfunction "1_1") (pintype "passive"))
      (node (ref "Q") (pin "1") (pinfunction "OSC1_1") (pintype "passive"))
      (node (ref "Upic") (pin "49") (pinfunction "OSC1/CLKI_49") (pintype "input"))
    )
    (net (code "60") (name "Net-(Q-OSC2)") (class "Default")
      (node (ref "Cq1") (pin "1") (pinfunction "1_1") (pintype "passive"))
      (node (ref "Q") (pin "2") (pinfunction "OSC2_2") (pintype "passive"))
      (node (ref "Upic") (pin "50") (pinfunction "OSC2/CLKO/RC15_50") (pintype "bidirectional"))
    )
    (net (code "61") (name "Net-(Qir-D)") (class "Default")
      (node (ref "Qir") (pin "3") (pinfunction "D_3") (pintype "passive"))
      (node (ref "QirOFF") (pin "2") (pinfunction "S_2") (pintype "passive"))
    )
    (net (code "62") (name "Net-(Qir-G)") (class "Default")
      (node (ref "Porte ET") (pin "5") (pinfunction "5_5") (pintype "passive"))
      (node (ref "Qir") (pin "1") (pinfunction "G_1") (pintype "passive"))
    )
    (net (code "63") (name "Net-(QirOFF-D)") (class "Default")
      (node (ref "QirOFF") (pin "3") (pinfunction "D_3") (pintype "passive"))
      (node (ref "QirON") (pin "3") (pinfunction "D_3") (pintype "passive"))
      (node (ref "Rsave") (pin "1") (pinfunction "1_1") (pintype "passive"))
    )
    (net (code "64") (name "Net-(RledIR-TAP)") (class "Default")
      (node (ref "RledIR") (pin "2") (pinfunction "TAP_2") (pintype "passive"))
      (node (ref "Rsave") (pin "2") (pinfunction "2_2") (pintype "passive"))
    )
    (net (code "65") (name "Net-(RledIR-TOP)") (class "Default")
      (node (ref "DIR") (pin "2") (pinfunction "2_2") (pintype "passive"))
      (node (ref "RledIR") (pin "1") (pinfunction "TOP_1") (pintype "passive"))
    )
    (net (code "66") (name "Net-(Rset33a-Pad1)") (class "Default")
      (node (ref "Rset33a") (pin "1") (pinfunction "1_1") (pintype "passive"))
      (node (ref "Rset33b") (pin "2") (pinfunction "2_2") (pintype "passive"))
    )
    (net (code "67") (name "Net-(Rset33b-Pad1)") (class "Default")
      (node (ref "Rset33b") (pin "1") (pinfunction "1_1") (pintype "passive"))
      (node (ref "Rset33c") (pin "2") (pinfunction "2_2") (pintype "passive"))
    )
    (net (code "68") (name "Net-(Rset455a-Pad1)") (class "Default")
      (node (ref "Rset455a") (pin "1") (pinfunction "1_1") (pintype "passive"))
      (node (ref "Rset455b") (pin "2") (pinfunction "2_2") (pintype "passive"))
    )
    (net (code "69") (name "Net-(Rset455b-Pad1)") (class "Default")
      (node (ref "Rset455b") (pin "1") (pinfunction "1_1") (pintype "passive"))
      (node (ref "Rset455c") (pin "2") (pinfunction "2_2") (pintype "passive"))
    )
    (net (code "70") (name "Net-(Rset455c-Pad1)") (class "Default")
      (node (ref "Rset455c") (pin "1") (pinfunction "1_1") (pintype "passive"))
      (node (ref "Rset455d") (pin "2") (pinfunction "2_2") (pintype "passive"))
    )
    (net (code "71") (name "Net-(Rsynchro-Pad1)") (class "Default")
      (node (ref "Rsynchro") (pin "1") (pinfunction "1_1") (pintype "passive"))
      (node (ref "SYNCHRO") (pin "1") (pinfunction "1_1") (pintype "passive"))
    )
    (net (code "72") (name "Net-(Umot-OUT1)") (class "Default")
      (node (ref "MOTEUR") (pin "1") (pinfunction "1_1") (pintype "passive"))
      (node (ref "Umot") (pin "1") (pinfunction "OUT1_1") (pintype "output"))
    )
    (net (code "73") (name "Net-(Umot-OUT2)") (class "Default")
      (node (ref "MOTEUR") (pin "2") (pinfunction "2_2") (pintype "passive"))
      (node (ref "Umot") (pin "7") (pinfunction "OUT2_7") (pintype "output"))
    )
    (net (code "74") (name "Net-(Upic-C2RX{slash}RG0)") (class "Default")
      (node (ref "Interrupteur") (pin "1") (pinfunction "1_1") (pintype "passive"))
      (node (ref "RintPu") (pin "2") (pinfunction "2_2") (pintype "passive"))
      (node (ref "Upic") (pin "75") (pinfunction "C2RX/RG0_75") (pintype "bidirectional"))
    )
    (net (code "75") (name "Net-(Upic-C2TX{slash}RG1)") (class "Default")
      (node (ref "Interrupteur") (pin "2") (pinfunction "2_2") (pintype "passive"))
      (node (ref "RintPd") (pin "1") (pinfunction "1_1") (pintype "passive"))
      (node (ref "Upic") (pin "74") (pinfunction "C2TX/RG1_74") (pintype "bidirectional"))
    )
    (net (code "76") (name "Net-(Upic-EMUC3{slash}SCK1{slash}INT0{slash}RF6)") (class "Default")
      (node (ref "Csynchro") (pin "2") (pinfunction "2_2") (pintype "passive"))
      (node (ref "Rsynchro") (pin "2") (pinfunction "2_2") (pintype "passive"))
      (node (ref "Upic") (pin "43") (pinfunction "EMUD3/SDO1/RF8_43") (pintype "bidirectional"))
      (node (ref "Upic") (pin "45") (pinfunction "EMUC3/SCK1/INT0/RF6_45") (pintype "bidirectional"))
    )
    (net (code "77") (name "VCC") (class "Default")
      (node (ref "ALIM") (pin "1") (pinfunction "B1_1") (pintype "passive"))
      (node (ref "Cin") (pin "2") (pinfunction "2_2") (pintype "passive"))
      (node (ref "Cin2") (pin "2") (pinfunction "2_2") (pintype "passive"))
      (node (ref "Cmot") (pin "2") (pinfunction "2_2") (pintype "passive"))
      (node (ref "Cus") (pin "2") (pinfunction "2_2") (pintype "passive"))
      (node (ref "U_US") (pin "2") (pinfunction "VCC_2") (pintype "power_in"))
      (node (ref "U_US") (pin "3") (pinfunction "VCC_3") (pintype "power_in"))
      (node (ref "U_US") (pin "6") (pinfunction "VREF_6") (pintype "bidirectional"))
      (node (ref "Umot") (pin "2") (pinfunction "VCC_2") (pintype "power_in"))
      (node (ref "Umot") (pin "3") (pinfunction "VCC_3") (pintype "power_in"))
      (node (ref "Umot") (pin "6") (pinfunction "VREF_6") (pintype "bidirectional"))
      (node (ref "Ureg") (pin "1") (pinfunction "IN_1") (pintype "power_in"))
    )
    (net (code "78") (name "Vdd") (class "Default")
      (node (ref "Ccod") (pin "2") (pinfunction "2_2") (pintype "passive"))
      (node (ref "Cd33") (pin "2") (pinfunction "2_2") (pintype "passive"))
      (node (ref "Cdpic1") (pin "1") (pinfunction "1_1") (pintype "passive"))
      (node (ref "Cdpic2") (pin "1") (pinfunction "1_1") (pintype "passive"))
      (node (ref "Cdpic3") (pin "1") (pinfunction "1_1") (pintype "passive"))
      (node (ref "Cdpic4") (pin "1") (pinfunction "1_1") (pintype "passive"))
      (node (ref "Codeur") (pin "4") (pinfunction "4_4") (pintype "passive"))
      (node (ref "Cout") (pin "2") (pinfunction "2_2") (pintype "passive"))
      (node (ref "Cout2") (pin "2") (pinfunction "2_2") (pintype "passive"))
      (node (ref "DIR") (pin "1") (pinfunction "1_1") (pintype "passive"))
      (node (ref "ICSP") (pin "2") (pinfunction "2_2") (pintype "passive"))
      (node (ref "OSC3.3") (pin "1") (pinfunction "1_1") (pintype "passive"))
      (node (ref "OSC3.3") (pin "4") (pinfunction "4_4") (pintype "passive"))
      (node (ref "Porte ET") (pin "6") (pinfunction "6_6") (pintype "passive"))
      (node (ref "Rd455") (pin "2") (pinfunction "2_2") (pintype "passive"))
      (node (ref "RdOR") (pin "2") (pinfunction "2_2") (pintype "passive"))
      (node (ref "RintPu") (pin "1") (pinfunction "1_1") (pintype "passive"))
      (node (ref "Rmclr") (pin "2") (pinfunction "2_2") (pintype "passive"))
      (node (ref "Rpbt1") (pin "2") (pinfunction "2_2") (pintype "passive"))
      (node (ref "Rqoff") (pin "2") (pinfunction "2_2") (pintype "passive"))
      (node (ref "Rset33a") (pin "2") (pinfunction "2_2") (pintype "passive"))
      (node (ref "Ru1rx") (pin "2") (pinfunction "2_2") (pintype "passive"))
      (node (ref "Ru1tx") (pin "2") (pinfunction "2_2") (pintype "passive"))
      (node (ref "UART") (pin "1") (pinfunction "1_1") (pintype "passive"))
      (node (ref "Upic") (pin "12") (pinfunction "VDD_12") (pintype "power_in"))
      (node (ref "Upic") (pin "24") (pinfunction "VREF+/RA10_24") (pintype "bidirectional"))
      (node (ref "Upic") (pin "25") (pinfunction "AVDD_25") (pintype "power_in"))
      (node (ref "Upic") (pin "32") (pinfunction "VDD_32") (pintype "power_in"))
      (node (ref "Upic") (pin "48") (pinfunction "VDD_48") (pintype "power_in"))
      (node (ref "Upic") (pin "71") (pinfunction "VDD_71") (pintype "power_in"))
      (node (ref "Ureg") (pin "3") (pinfunction "OUT_3") (pintype "power_in"))
    )
    (net (code "79") (name "unconnected-(ICSP-Pad6)") (class "Default")
      (node (ref "ICSP") (pin "6") (pinfunction "6_6") (pintype "passive"))
    )
    (net (code "80") (name "unconnected-(OSC3.3-Pad5)") (class "Default")
      (node (ref "OSC3.3") (pin "5") (pinfunction "5_5") (pintype "passive"))
    )
    (net (code "81") (name "unconnected-(Porte ET-Pad4)") (class "Default")
      (node (ref "Porte ET") (pin "4") (pinfunction "4_4") (pintype "passive"))
    )
    (net (code "82") (name "unconnected-(RledIR-BOT-Pad3)") (class "Default")
      (node (ref "RledIR") (pin "3") (pinfunction "BOT_3") (pintype "passive"))
    )
    (net (code "83") (name "unconnected-(Upic-AN6{slash}OCFA{slash}RB6-Pad21)") (class "Default")
      (node (ref "Upic") (pin "21") (pinfunction "AN6/OCFA/RB6_21") (pintype "bidirectional+no_connect"))
    )
    (net (code "84") (name "unconnected-(Upic-AN7{slash}RB7-Pad22)") (class "Default")
      (node (ref "Upic") (pin "22") (pinfunction "AN7/RB7_22") (pintype "bidirectional+no_connect"))
    )
    (net (code "85") (name "unconnected-(Upic-EMUC1{slash}SOSCO{slash}T1CK{slash}CN0{slash}RC14-Pad60)") (class "Default")
      (node (ref "Upic") (pin "60") (pinfunction "EMUC1/SOSCO/T1CK/CN0/RC14_60") (pintype "bidirectional+no_connect"))
    )
    (net (code "86") (name "unconnected-(Upic-EMUD1{slash}SOSCI{slash}CN1{slash}RC13-Pad59)") (class "Default")
      (node (ref "Upic") (pin "59") (pinfunction "EMUD1/SOSCI/CN1/RC13_59") (pintype "bidirectional+no_connect"))
    )
    (net (code "87") (name "unconnected-(Upic-EMUD2{slash}OC2{slash}RD1-Pad61)") (class "Default")
      (node (ref "Upic") (pin "61") (pinfunction "EMUD2/OC2/RD1_61") (pintype "bidirectional+no_connect"))
    )
    (net (code "88") (name "unconnected-(Upic-IC7{slash}CN20{slash}RD14-Pad37)") (class "Default")
      (node (ref "Upic") (pin "37") (pinfunction "IC7/CN20/RD14_37") (pintype "bidirectional+no_connect"))
    )
    (net (code "89") (name "unconnected-(Upic-IC8{slash}CN21{slash}RD15-Pad38)") (class "Default")
      (node (ref "Upic") (pin "38") (pinfunction "IC8/CN21/RD15_38") (pintype "bidirectional+no_connect"))
    )
    (net (code "90") (name "unconnected-(Upic-OC3{slash}RD2-Pad62)") (class "Default")
      (node (ref "Upic") (pin "62") (pinfunction "OC3/RD2_62") (pintype "bidirectional+no_connect"))
    )
    (net (code "91") (name "unconnected-(Upic-OC4{slash}RD3-Pad63)") (class "Default")
      (node (ref "Upic") (pin "63") (pinfunction "OC4/RD3_63") (pintype "bidirectional+no_connect"))
    )
    (net (code "92") (name "unconnected-(Upic-OC5{slash}CN13{slash}RD4-Pad66)") (class "Default")
      (node (ref "Upic") (pin "66") (pinfunction "OC5/CN13/RD4_66") (pintype "bidirectional"))
    )
    (net (code "93") (name "unconnected-(Upic-OC6{slash}CN14{slash}RD5-Pad67)") (class "Default")
      (node (ref "Upic") (pin "67") (pinfunction "OC6/CN14/RD5_67") (pintype "bidirectional"))
    )
    (net (code "94") (name "unconnected-(Upic-OC7{slash}CN15{slash}RD6-Pad68)") (class "Default")
      (node (ref "Upic") (pin "68") (pinfunction "OC7/CN15/RD6_68") (pintype "bidirectional"))
    )
    (net (code "95") (name "unconnected-(Upic-OC8{slash}UPDN{slash}CN16{slash}RD7-Pad69)") (class "Default")
      (node (ref "Upic") (pin "69") (pinfunction "OC8/UPDN/CN16/RD7_69") (pintype "bidirectional"))
    )
    (net (code "96") (name "unconnected-(Upic-PWM3H{slash}RE5-Pad1)") (class "Default")
      (node (ref "Upic") (pin "1") (pinfunction "PWM3H/RE5_1") (pintype "bidirectional"))
    )
    (net (code "97") (name "unconnected-(Upic-PWM3L{slash}RE4-Pad80)") (class "Default")
      (node (ref "Upic") (pin "80") (pinfunction "PWM3L/RE4_80") (pintype "bidirectional"))
    )
    (net (code "98") (name "unconnected-(Upic-SDI1{slash}RF7-Pad44)") (class "Default")
      (node (ref "Upic") (pin "44") (pinfunction "SDI1/RF7_44") (pintype "bidirectional+no_connect"))
    )
    (net (code "99") (name "unconnected-(Upic-T2CK{slash}RC1-Pad4)") (class "Default")
      (node (ref "Upic") (pin "4") (pinfunction "T2CK/RC1_4") (pintype "bidirectional+no_connect"))
    )
    (net (code "100") (name "unconnected-(Upic-T4CK{slash}RC3-Pad5)") (class "Default")
      (node (ref "Upic") (pin "5") (pinfunction "T4CK/RC3_5") (pintype "bidirectional+no_connect"))
    )
  )
)
